# MotorControl.net
KiCad netlist of a schematic drawn in EAGLE
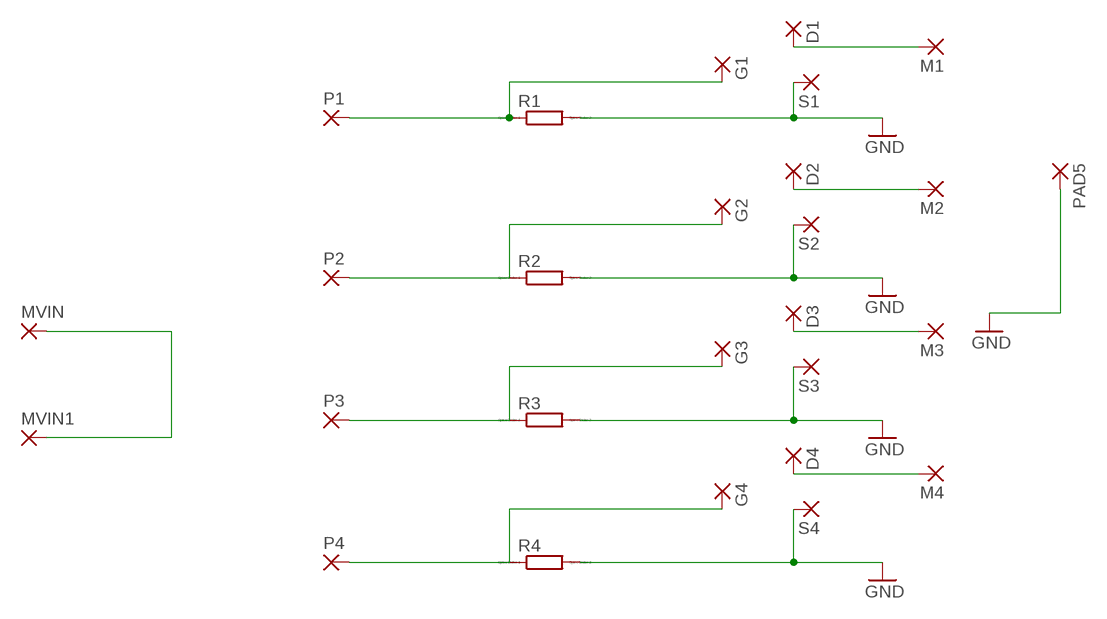
[diagram p0: schematic, sheet 1]

(export (version "E")
  (design (tool "Eeschema 10.0.6"))
  (components
    (comp (ref "D1")
      (value "1,6/0,8")
      (footprint "eagle-import:1,6_0,8")
      (libsource (lib "eagle-import") (part "1,6/0,8"))
    )
    (comp (ref "D2")
      (value "1,6/0,8")
      (footprint "eagle-import:1,6_0,8")
      (libsource (lib "eagle-import") (part "1,6/0,8"))
    )
    (comp (ref "D3")
      (value "1,6/0,8")
      (footprint "eagle-import:1,6_0,8")
      (libsource (lib "eagle-import") (part "1,6/0,8"))
    )
    (comp (ref "D4")
      (value "1,6/0,8")
      (footprint "eagle-import:1,6_0,8")
      (libsource (lib "eagle-import") (part "1,6/0,8"))
    )
    (comp (ref "G1")
      (value "1,6/0,8")
      (footprint "eagle-import:1,6_0,8")
      (libsource (lib "eagle-import") (part "1,6/0,8"))
    )
    (comp (ref "G2")
      (value "1,6/0,8")
      (footprint "eagle-import:1,6_0,8")
      (libsource (lib "eagle-import") (part "1,6/0,8"))
    )
    (comp (ref "G3")
      (value "1,6/0,8")
      (footprint "eagle-import:1,6_0,8")
      (libsource (lib "eagle-import") (part "1,6/0,8"))
    )
    (comp (ref "G4")
      (value "1,6/0,8")
      (footprint "eagle-import:1,6_0,8")
      (libsource (lib "eagle-import") (part "1,6/0,8"))
    )
    (comp (ref "M1")
      (value "2,15/1,0")
      (footprint "eagle-import:2,15_1,0")
      (libsource (lib "eagle-import") (part "2,15/1,0"))
    )
    (comp (ref "M2")
      (value "2,15/1,0")
      (footprint "eagle-import:2,15_1,0")
      (libsource (lib "eagle-import") (part "2,15/1,0"))
    )
    (comp (ref "M3")
      (value "2,15/1,0")
      (footprint "eagle-import:2,15_1,0")
      (libsource (lib "eagle-import") (part "2,15/1,0"))
    )
    (comp (ref "M4")
      (value "2,15/1,0")
      (footprint "eagle-import:2,15_1,0")
      (libsource (lib "eagle-import") (part "2,15/1,0"))
    )
    (comp (ref "MVIN")
      (value "2,15/1,0")
      (footprint "eagle-import:2,15_1,0")
      (libsource (lib "eagle-import") (part "2,15/1,0"))
    )
    (comp (ref "MVIN1")
      (value "2,15/1,0")
      (footprint "eagle-import:2,15_1,0")
      (libsource (lib "eagle-import") (part "2,15/1,0"))
    )
    (comp (ref "P1")
      (value "2,15/1,0")
      (footprint "eagle-import:2,15_1,0")
      (libsource (lib "eagle-import") (part "2,15/1,0"))
    )
    (comp (ref "P2")
      (value "2,15/1,0")
      (footprint "eagle-import:2,15_1,0")
      (libsource (lib "eagle-import") (part "2,15/1,0"))
    )
    (comp (ref "P3")
      (value "2,15/1,0")
      (footprint "eagle-import:2,15_1,0")
      (libsource (lib "eagle-import") (part "2,15/1,0"))
    )
    (comp (ref "P4")
      (value "2,15/1,0")
      (footprint "eagle-import:2,15_1,0")
      (libsource (lib "eagle-import") (part "2,15/1,0"))
    )
    (comp (ref "PAD5")
      (value "2,15/1,0")
      (footprint "eagle-import:2,15_1,0")
      (libsource (lib "eagle-import") (part "2,15/1,0"))
    )
    (comp (ref "R1")
      (value "R0207/10")
      (footprint "eagle-import:0207_10")
      (libsource (lib "eagle-import") (part "R0207/10"))
    )
    (comp (ref "R2")
      (value "R0207/10")
      (footprint "eagle-import:0207_10")
      (libsource (lib "eagle-import") (part "R0207/10"))
    )
    (comp (ref "R3")
      (value "R0207/10")
      (footprint "eagle-import:0207_10")
      (libsource (lib "eagle-import") (part "R0207/10"))
    )
    (comp (ref "R4")
      (value "R0207/10")
      (footprint "eagle-import:0207_10")
      (libsource (lib "eagle-import") (part "R0207/10"))
    )
    (comp (ref "S1")
      (value "1,6/0,8")
      (footprint "eagle-import:1,6_0,8")
      (libsource (lib "eagle-import") (part "1,6/0,8"))
    )
    (comp (ref "S2")
      (value "1,6/0,8")
      (footprint "eagle-import:1,6_0,8")
      (libsource (lib "eagle-import") (part "1,6/0,8"))
    )
    (comp (ref "S3")
      (value "1,6/0,8")
      (footprint "eagle-import:1,6_0,8")
      (libsource (lib "eagle-import") (part "1,6/0,8"))
    )
    (comp (ref "S4")
      (value "1,6/0,8")
      (footprint "eagle-import:1,6_0,8")
      (libsource (lib "eagle-import") (part "1,6/0,8"))
    )
  )
  (nets
    (net (code "1") (name "GND") (class "Default")
      (node (ref "PAD5") (pin "1") (pinfunction "P_1") (pintype "passive"))
      (node (ref "R1") (pin "2") (pinfunction "2_2") (pintype "passive"))
      (node (ref "R2") (pin "2") (pinfunction "2_2") (pintype "passive"))
      (node (ref "R3") (pin "2") (pinfunction "2_2") (pintype "passive"))
      (node (ref "R4") (pin "2") (pinfunction "2_2") (pintype "passive"))
      (node (ref "S1") (pin "1") (pinfunction "P_1") (pintype "passive"))
      (node (ref "S2") (pin "1") (pinfunction "P_1") (pintype "passive"))
      (node (ref "S3") (pin "1") (pinfunction "P_1") (pintype "passive"))
      (node (ref "S4") (pin "1") (pinfunction "P_1") (pintype "passive"))
    )
    (net (code "2") (name "Net-(D1-P)") (class "Default")
      (node (ref "D1") (pin "1") (pinfunction "P_1") (pintype "passive"))
      (node (ref "M1") (pin "1") (pinfunction "P_1") (pintype "passive"))
    )
    (net (code "3") (name "Net-(D2-P)") (class "Default")
      (node (ref "D2") (pin "1") (pinfunction "P_1") (pintype "passive"))
      (node (ref "M2") (pin "1") (pinfunction "P_1") (pintype "passive"))
    )
    (net (code "4") (name "Net-(D3-P)") (class "Default")
      (node (ref "D3") (pin "1") (pinfunction "P_1") (pintype "passive"))
      (node (ref "M3") (pin "1") (pinfunction "P_1") (pintype "passive"))
    )
    (net (code "5") (name "Net-(D4-P)") (class "Default")
      (node (ref "D4") (pin "1") (pinfunction "P_1") (pintype "passive"))
      (node (ref "M4") (pin "1") (pinfunction "P_1") (pintype "passive"))
    )
    (net (code "6") (name "Net-(G1-P)") (class "Default")
      (node (ref "G1") (pin "1") (pinfunction "P_1") (pintype "passive"))
      (node (ref "P1") (pin "1") (pinfunction "P_1") (pintype "passive"))
      (node (ref "R1") (pin "1") (pinfunction "1_1") (pintype "passive"))
    )
    (net (code "7") (name "Net-(G2-P)") (class "Default")
      (node (ref "G2") (pin "1") (pinfunction "P_1") (pintype "passive"))
      (node (ref "P2") (pin "1") (pinfunction "P_1") (pintype "passive"))
      (node (ref "R2") (pin "1") (pinfunction "1_1") (pintype "passive"))
    )
    (net (code "8") (name "Net-(G3-P)") (class "Default")
      (node (ref "G3") (pin "1") (pinfunction "P_1") (pintype "passive"))
      (node (ref "P3") (pin "1") (pinfunction "P_1") (pintype "passive"))
      (node (ref "R3") (pin "1") (pinfunction "1_1") (pintype "passive"))
    )
    (net (code "9") (name "Net-(G4-P)") (class "Default")
      (node (ref "G4") (pin "1") (pinfunction "P_1") (pintype "passive"))
      (node (ref "P4") (pin "1") (pinfunction "P_1") (pintype "passive"))
      (node (ref "R4") (pin "1") (pinfunction "1_1") (pintype "passive"))
    )
    (net (code "10") (name "Net-(MVIN-P)") (class "Default")
      (node (ref "MVIN") (pin "1") (pinfunction "P_1") (pintype "passive"))
      (node (ref "MVIN1") (pin "1") (pinfunction "P_1") (pintype "passive"))
    )
  )
)
